# lumiere_ctrl_shematic.net
KiCad netlist of a schematic drawn in Altium Designer
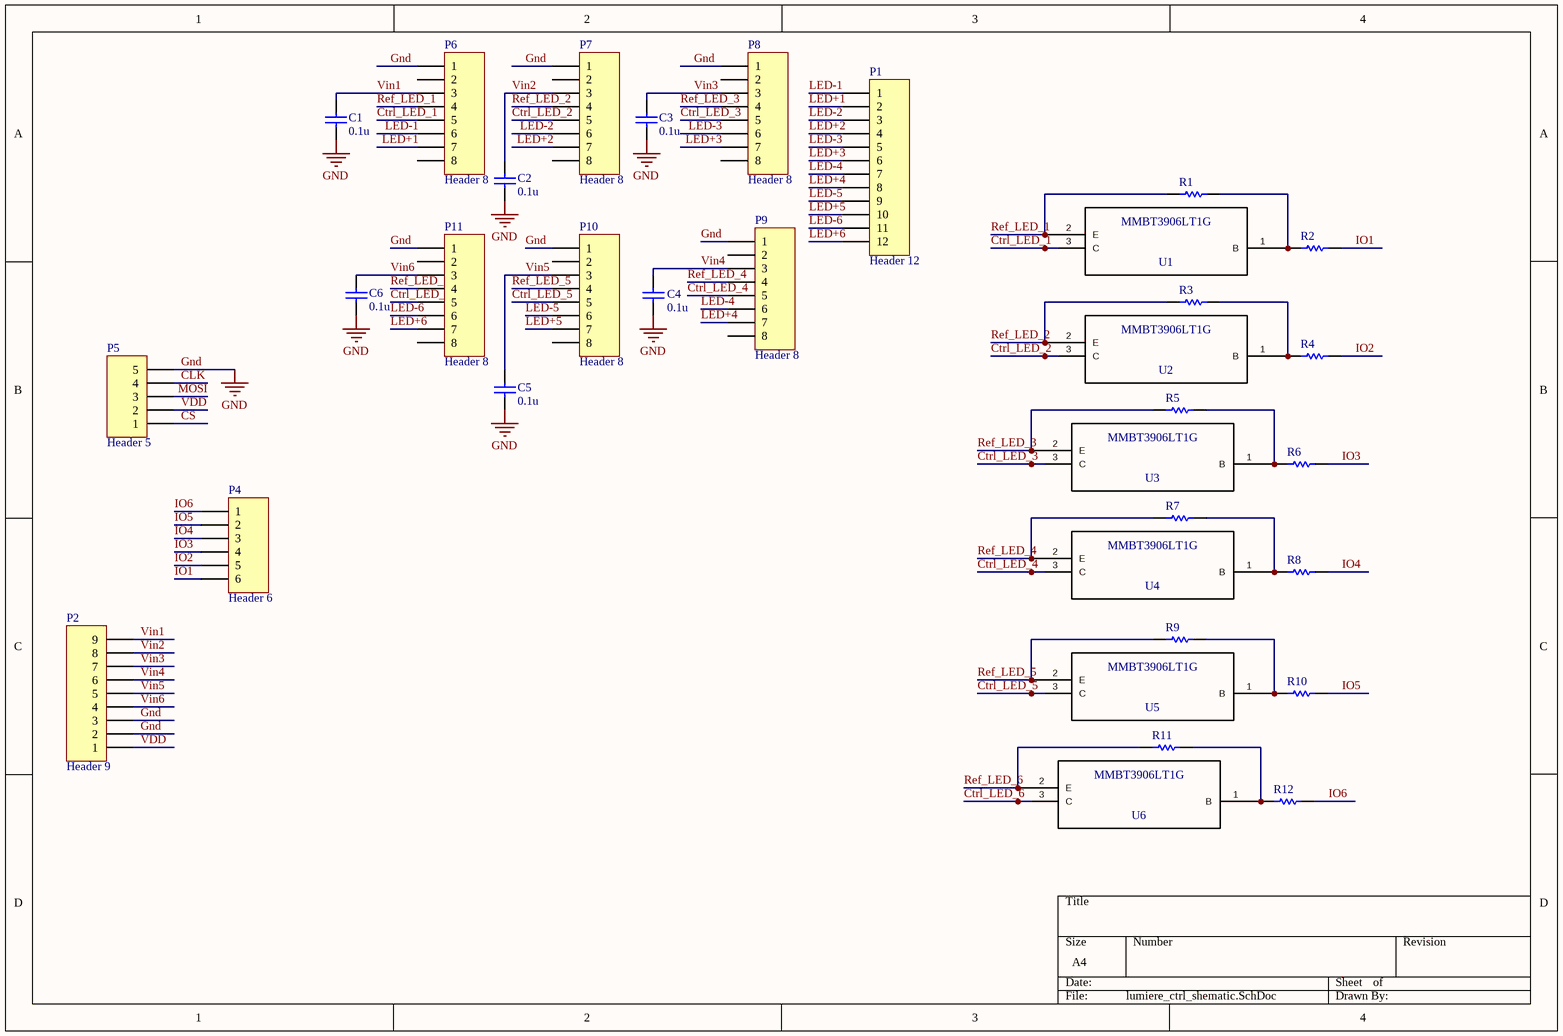
[diagram p0: lumiere_ctrl_shematic.SchDoc]

(export (version "E")
  (design (tool "Eeschema 10.0.6"))
  (components
    (comp (ref "C1")
      (value "0.1u")
      (footprint "CC1206N")
      (description "Capacitor")
      (fields (field (name "VOLTAGE") "50V") (field (name "Comment") "CapSMD"))
      (libsource (lib "S3_projet") (part "CapSMD"))
    )
    (comp (ref "C2")
      (value "0.1u")
      (footprint "CC1206N")
      (description "Capacitor")
      (fields (field (name "VOLTAGE") "50V") (field (name "Comment") "CapSMD"))
      (libsource (lib "S3_projet") (part "CapSMD"))
    )
    (comp (ref "C3")
      (value "0.1u")
      (footprint "CC1206N")
      (description "Capacitor")
      (fields (field (name "VOLTAGE") "50V") (field (name "Comment") "CapSMD"))
      (libsource (lib "S3_projet") (part "CapSMD"))
    )
    (comp (ref "C4")
      (value "0.1u")
      (footprint "CC1206N")
      (description "Capacitor")
      (fields (field (name "VOLTAGE") "50V") (field (name "Comment") "CapSMD"))
      (libsource (lib "S3_projet") (part "CapSMD"))
    )
    (comp (ref "C5")
      (value "0.1u")
      (footprint "CC1206N")
      (description "Capacitor")
      (fields (field (name "VOLTAGE") "50V") (field (name "Comment") "CapSMD"))
      (libsource (lib "S3_projet") (part "CapSMD"))
    )
    (comp (ref "C6")
      (value "0.1u")
      (footprint "CC1206N")
      (description "Capacitor")
      (fields (field (name "VOLTAGE") "50V") (field (name "Comment") "CapSMD"))
      (libsource (lib "S3_projet") (part "CapSMD"))
    )
    (comp (ref "P1")
      (value "Header 12")
      (footprint "Terminal block 12 pos")
      (description "Header, 12-Pin")
      (fields (field (name "PUBLISHER") "Altium Limited"))
      (libsource (lib "Miscellaneous Connectors") (part "Header 12"))
    )
    (comp (ref "P2")
      (value "Header 9")
      (footprint "Terminal block 9 pos")
      (description "Header, 9-Pin")
      (fields (field (name "PUBLISHER") "Altium Limited"))
      (libsource (lib "Miscellaneous Connectors") (part "Header 9"))
    )
    (comp (ref "P4")
      (value "Header 6")
      (footprint "HDR1X6")
      (description "Header, 6-Pin")
      (fields (field (name "PUBLISHER") "Altium Limited"))
      (libsource (lib "Miscellaneous Connectors") (part "Header 6"))
    )
    (comp (ref "P5")
      (value "Header 5")
      (footprint "HDR1X5")
      (description "Header, 5-Pin")
      (fields (field (name "PUBLISHER") "Altium Limited"))
      (libsource (lib "Miscellaneous Connectors") (part "Header 5"))
    )
    (comp (ref "P6")
      (value "Header 8")
      (footprint "HDR1X8")
      (description "Header, 8-Pin")
      (fields (field (name "PUBLISHER") "Altium Limited"))
      (libsource (lib "Miscellaneous Connectors") (part "Header 8"))
    )
    (comp (ref "P7")
      (value "Header 8")
      (footprint "HDR1X8")
      (description "Header, 8-Pin")
      (fields (field (name "PUBLISHER") "Altium Limited"))
      (libsource (lib "Miscellaneous Connectors") (part "Header 8"))
    )
    (comp (ref "P8")
      (value "Header 8")
      (footprint "HDR1X8")
      (description "Header, 8-Pin")
      (fields (field (name "PUBLISHER") "Altium Limited"))
      (libsource (lib "Miscellaneous Connectors") (part "Header 8"))
    )
    (comp (ref "P9")
      (value "Header 8")
      (footprint "HDR1X8")
      (description "Header, 8-Pin")
      (fields (field (name "PUBLISHER") "Altium Limited"))
      (libsource (lib "Miscellaneous Connectors") (part "Header 8"))
    )
    (comp (ref "P10")
      (value "Header 8")
      (footprint "HDR1X8")
      (description "Header, 8-Pin")
      (fields (field (name "PUBLISHER") "Altium Limited"))
      (libsource (lib "Miscellaneous Connectors") (part "Header 8"))
    )
    (comp (ref "P11")
      (value "Header 8")
      (footprint "HDR1X8")
      (description "Header, 8-Pin")
      (fields (field (name "PUBLISHER") "Altium Limited"))
      (libsource (lib "Miscellaneous Connectors") (part "Header 8"))
    )
    (comp (ref "R1")
      (value "ResSMD")
      (footprint "STA_RMCF1206")
      (libsource (lib "S3_projet") (part "ResSMD"))
    )
    (comp (ref "R2")
      (value "ResSMD")
      (footprint "STA_RMCF1206")
      (libsource (lib "S3_projet") (part "ResSMD"))
    )
    (comp (ref "R3")
      (value "ResSMD")
      (footprint "STA_RMCF1206")
      (libsource (lib "S3_projet") (part "ResSMD"))
    )
    (comp (ref "R4")
      (value "ResSMD")
      (footprint "STA_RMCF1206")
      (libsource (lib "S3_projet") (part "ResSMD"))
    )
    (comp (ref "R5")
      (value "ResSMD")
      (footprint "STA_RMCF1206")
      (libsource (lib "S3_projet") (part "ResSMD"))
    )
    (comp (ref "R6")
      (value "ResSMD")
      (footprint "STA_RMCF1206")
      (libsource (lib "S3_projet") (part "ResSMD"))
    )
    (comp (ref "R7")
      (value "ResSMD")
      (footprint "STA_RMCF1206")
      (libsource (lib "S3_projet") (part "ResSMD"))
    )
    (comp (ref "R8")
      (value "ResSMD")
      (footprint "STA_RMCF1206")
      (libsource (lib "S3_projet") (part "ResSMD"))
    )
    (comp (ref "R9")
      (value "ResSMD")
      (footprint "STA_RMCF1206")
      (libsource (lib "S3_projet") (part "ResSMD"))
    )
    (comp (ref "R10")
      (value "ResSMD")
      (footprint "STA_RMCF1206")
      (libsource (lib "S3_projet") (part "ResSMD"))
    )
    (comp (ref "R11")
      (value "ResSMD")
      (footprint "STA_RMCF1206")
      (libsource (lib "S3_projet") (part "ResSMD"))
    )
    (comp (ref "R12")
      (value "ResSMD")
      (footprint "STA_RMCF1206")
      (libsource (lib "S3_projet") (part "ResSMD"))
    )
    (comp (ref "U1")
      (value "MMBT3906LT1G")
      (footprint "SOT-23")
      (libsource (lib "AltiumV15") (part "MMBT3906LT1G"))
    )
    (comp (ref "U2")
      (value "MMBT3906LT1G")
      (footprint "SOT-23")
      (libsource (lib "AltiumV15") (part "MMBT3906LT1G"))
    )
    (comp (ref "U3")
      (value "MMBT3906LT1G")
      (footprint "SOT-23")
      (libsource (lib "AltiumV15") (part "MMBT3906LT1G"))
    )
    (comp (ref "U4")
      (value "MMBT3906LT1G")
      (footprint "SOT-23")
      (libsource (lib "AltiumV15") (part "MMBT3906LT1G"))
    )
    (comp (ref "U5")
      (value "MMBT3906LT1G")
      (footprint "SOT-23")
      (libsource (lib "AltiumV15") (part "MMBT3906LT1G"))
    )
    (comp (ref "U6")
      (value "MMBT3906LT1G")
      (footprint "SOT-23")
      (libsource (lib "AltiumV15") (part "MMBT3906LT1G"))
    )
  )
  (nets
    (net (code "1") (name "/CLK") (class "Default")
      (node (ref "P5") (pin "4") (pinfunction "4_4") (pintype "passive"))
    )
    (net (code "2") (name "/CS") (class "Default")
      (node (ref "P5") (pin "1") (pinfunction "1_1") (pintype "passive"))
    )
    (net (code "3") (name "/Ctrl_LED_1") (class "Default")
      (node (ref "P6") (pin "5") (pinfunction "5_5") (pintype "passive"))
      (node (ref "U1") (pin "3") (pinfunction "C_3") (pintype "passive"))
    )
    (net (code "4") (name "/Ctrl_LED_2") (class "Default")
      (node (ref "P7") (pin "5") (pinfunction "5_5") (pintype "passive"))
      (node (ref "U2") (pin "3") (pinfunction "C_3") (pintype "passive"))
    )
    (net (code "5") (name "/Ctrl_LED_3") (class "Default")
      (node (ref "P8") (pin "5") (pinfunction "5_5") (pintype "passive"))
      (node (ref "U3") (pin "3") (pinfunction "C_3") (pintype "passive"))
    )
    (net (code "6") (name "/Ctrl_LED_4") (class "Default")
      (node (ref "P9") (pin "5") (pinfunction "5_5") (pintype "passive"))
      (node (ref "U4") (pin "3") (pinfunction "C_3") (pintype "passive"))
    )
    (net (code "7") (name "/Ctrl_LED_5") (class "Default")
      (node (ref "P10") (pin "5") (pinfunction "5_5") (pintype "passive"))
      (node (ref "U5") (pin "3") (pinfunction "C_3") (pintype "passive"))
    )
    (net (code "8") (name "/Ctrl_LED_6") (class "Default")
      (node (ref "P11") (pin "5") (pinfunction "5_5") (pintype "passive"))
      (node (ref "U6") (pin "3") (pinfunction "C_3") (pintype "passive"))
    )
    (net (code "9") (name "/IO1") (class "Default")
      (node (ref "P4") (pin "6") (pinfunction "6_6") (pintype "passive"))
      (node (ref "R2") (pin "1") (pinfunction "1_1") (pintype "passive"))
    )
    (net (code "10") (name "/IO2") (class "Default")
      (node (ref "P4") (pin "5") (pinfunction "5_5") (pintype "passive"))
      (node (ref "R4") (pin "1") (pinfunction "1_1") (pintype "passive"))
    )
    (net (code "11") (name "/IO3") (class "Default")
      (node (ref "P4") (pin "4") (pinfunction "4_4") (pintype "passive"))
      (node (ref "R6") (pin "1") (pinfunction "1_1") (pintype "passive"))
    )
    (net (code "12") (name "/IO4") (class "Default")
      (node (ref "P4") (pin "3") (pinfunction "3_3") (pintype "passive"))
      (node (ref "R8") (pin "1") (pinfunction "1_1") (pintype "passive"))
    )
    (net (code "13") (name "/IO5") (class "Default")
      (node (ref "P4") (pin "2") (pinfunction "2_2") (pintype "passive"))
      (node (ref "R10") (pin "1") (pinfunction "1_1") (pintype "passive"))
    )
    (net (code "14") (name "/IO6") (class "Default")
      (node (ref "P4") (pin "1") (pinfunction "1_1") (pintype "passive"))
      (node (ref "R12") (pin "1") (pinfunction "1_1") (pintype "passive"))
    )
    (net (code "15") (name "/LED+1") (class "Default")
      (node (ref "P1") (pin "2") (pinfunction "2_2") (pintype "passive"))
      (node (ref "P6") (pin "7") (pinfunction "7_7") (pintype "passive"))
    )
    (net (code "16") (name "/LED+2") (class "Default")
      (node (ref "P1") (pin "4") (pinfunction "4_4") (pintype "passive"))
      (node (ref "P7") (pin "7") (pinfunction "7_7") (pintype "passive"))
    )
    (net (code "17") (name "/LED+3") (class "Default")
      (node (ref "P1") (pin "6") (pinfunction "6_6") (pintype "passive"))
      (node (ref "P8") (pin "7") (pinfunction "7_7") (pintype "passive"))
    )
    (net (code "18") (name "/LED+4") (class "Default")
      (node (ref "P1") (pin "8") (pinfunction "8_8") (pintype "passive"))
      (node (ref "P9") (pin "7") (pinfunction "7_7") (pintype "passive"))
    )
    (net (code "19") (name "/LED+5") (class "Default")
      (node (ref "P1") (pin "10") (pinfunction "10_10") (pintype "passive"))
      (node (ref "P10") (pin "7") (pinfunction "7_7") (pintype "passive"))
    )
    (net (code "20") (name "/LED+6") (class "Default")
      (node (ref "P1") (pin "12") (pinfunction "12_12") (pintype "passive"))
      (node (ref "P11") (pin "7") (pinfunction "7_7") (pintype "passive"))
    )
    (net (code "21") (name "/LED-1") (class "Default")
      (node (ref "P1") (pin "1") (pinfunction "1_1") (pintype "passive"))
      (node (ref "P6") (pin "6") (pinfunction "6_6") (pintype "passive"))
    )
    (net (code "22") (name "/LED-2") (class "Default")
      (node (ref "P1") (pin "3") (pinfunction "3_3") (pintype "passive"))
      (node (ref "P7") (pin "6") (pinfunction "6_6") (pintype "passive"))
    )
    (net (code "23") (name "/LED-3") (class "Default")
      (node (ref "P1") (pin "5") (pinfunction "5_5") (pintype "passive"))
      (node (ref "P8") (pin "6") (pinfunction "6_6") (pintype "passive"))
    )
    (net (code "24") (name "/LED-4") (class "Default")
      (node (ref "P1") (pin "7") (pinfunction "7_7") (pintype "passive"))
      (node (ref "P9") (pin "6") (pinfunction "6_6") (pintype "passive"))
    )
    (net (code "25") (name "/LED-5") (class "Default")
      (node (ref "P1") (pin "9") (pinfunction "9_9") (pintype "passive"))
      (node (ref "P10") (pin "6") (pinfunction "6_6") (pintype "passive"))
    )
    (net (code "26") (name "/LED-6") (class "Default")
      (node (ref "P1") (pin "11") (pinfunction "11_11") (pintype "passive"))
      (node (ref "P11") (pin "6") (pinfunction "6_6") (pintype "passive"))
    )
    (net (code "27") (name "/MOSI") (class "Default")
      (node (ref "P5") (pin "3") (pinfunction "3_3") (pintype "passive"))
    )
    (net (code "28") (name "/Ref_LED_1") (class "Default")
      (node (ref "P6") (pin "4") (pinfunction "4_4") (pintype "passive"))
      (node (ref "R1") (pin "2") (pinfunction "2_2") (pintype "passive"))
      (node (ref "U1") (pin "2") (pinfunction "E_2") (pintype "passive"))
    )
    (net (code "29") (name "/Ref_LED_2") (class "Default")
      (node (ref "P7") (pin "4") (pinfunction "4_4") (pintype "passive"))
      (node (ref "R3") (pin "2") (pinfunction "2_2") (pintype "passive"))
      (node (ref "U2") (pin "2") (pinfunction "E_2") (pintype "passive"))
    )
    (net (code "30") (name "/Ref_LED_3") (class "Default")
      (node (ref "P8") (pin "4") (pinfunction "4_4") (pintype "passive"))
      (node (ref "R5") (pin "2") (pinfunction "2_2") (pintype "passive"))
      (node (ref "U3") (pin "2") (pinfunction "E_2") (pintype "passive"))
    )
    (net (code "31") (name "/Ref_LED_4") (class "Default")
      (node (ref "P9") (pin "4") (pinfunction "4_4") (pintype "passive"))
      (node (ref "R7") (pin "2") (pinfunction "2_2") (pintype "passive"))
      (node (ref "U4") (pin "2") (pinfunction "E_2") (pintype "passive"))
    )
    (net (code "32") (name "/Ref_LED_5") (class "Default")
      (node (ref "P10") (pin "4") (pinfunction "4_4") (pintype "passive"))
      (node (ref "R9") (pin "2") (pinfunction "2_2") (pintype "passive"))
      (node (ref "U5") (pin "2") (pinfunction "E_2") (pintype "passive"))
    )
    (net (code "33") (name "/Ref_LED_6") (class "Default")
      (node (ref "P11") (pin "4") (pinfunction "4_4") (pintype "passive"))
      (node (ref "R11") (pin "2") (pinfunction "2_2") (pintype "passive"))
      (node (ref "U6") (pin "2") (pinfunction "E_2") (pintype "passive"))
    )
    (net (code "34") (name "/VDD") (class "Default")
      (node (ref "P2") (pin "1") (pinfunction "1_1") (pintype "passive"))
      (node (ref "P5") (pin "2") (pinfunction "2_2") (pintype "passive"))
    )
    (net (code "35") (name "/Vin1") (class "Default")
      (node (ref "C1") (pin "2") (pinfunction "2_2") (pintype "passive"))
      (node (ref "P2") (pin "9") (pinfunction "9_9") (pintype "passive"))
      (node (ref "P6") (pin "3") (pinfunction "3_3") (pintype "passive"))
    )
    (net (code "36") (name "/Vin2") (class "Default")
      (node (ref "C2") (pin "2") (pinfunction "2_2") (pintype "passive"))
      (node (ref "P2") (pin "8") (pinfunction "8_8") (pintype "passive"))
      (node (ref "P7") (pin "3") (pinfunction "3_3") (pintype "passive"))
    )
    (net (code "37") (name "/Vin3") (class "Default")
      (node (ref "C3") (pin "2") (pinfunction "2_2") (pintype "passive"))
      (node (ref "P2") (pin "7") (pinfunction "7_7") (pintype "passive"))
      (node (ref "P8") (pin "3") (pinfunction "3_3") (pintype "passive"))
    )
    (net (code "38") (name "/Vin4") (class "Default")
      (node (ref "C4") (pin "2") (pinfunction "2_2") (pintype "passive"))
      (node (ref "P2") (pin "6") (pinfunction "6_6") (pintype "passive"))
      (node (ref "P9") (pin "3") (pinfunction "3_3") (pintype "passive"))
    )
    (net (code "39") (name "/Vin5") (class "Default")
      (node (ref "C5") (pin "2") (pinfunction "2_2") (pintype "passive"))
      (node (ref "P10") (pin "3") (pinfunction "3_3") (pintype "passive"))
      (node (ref "P2") (pin "5") (pinfunction "5_5") (pintype "passive"))
    )
    (net (code "40") (name "/Vin6") (class "Default")
      (node (ref "C6") (pin "2") (pinfunction "2_2") (pintype "passive"))
      (node (ref "P11") (pin "3") (pinfunction "3_3") (pintype "passive"))
      (node (ref "P2") (pin "4") (pinfunction "4_4") (pintype "passive"))
    )
    (net (code "41") (name "GND") (class "Default")
      (node (ref "C1") (pin "1") (pinfunction "1_1") (pintype "passive"))
      (node (ref "C2") (pin "1") (pinfunction "1_1") (pintype "passive"))
      (node (ref "C3") (pin "1") (pinfunction "1_1") (pintype "passive"))
      (node (ref "C4") (pin "1") (pinfunction "1_1") (pintype "passive"))
      (node (ref "C5") (pin "1") (pinfunction "1_1") (pintype "passive"))
      (node (ref "C6") (pin "1") (pinfunction "1_1") (pintype "passive"))
      (node (ref "P10") (pin "1") (pinfunction "1_1") (pintype "passive"))
      (node (ref "P11") (pin "1") (pinfunction "1_1") (pintype "passive"))
      (node (ref "P2") (pin "2") (pinfunction "2_2") (pintype "passive"))
      (node (ref "P2") (pin "3") (pinfunction "3_3") (pintype "passive"))
      (node (ref "P5") (pin "5") (pinfunction "5_5") (pintype "passive"))
      (node (ref "P6") (pin "1") (pinfunction "1_1") (pintype "passive"))
      (node (ref "P7") (pin "1") (pinfunction "1_1") (pintype "passive"))
      (node (ref "P8") (pin "1") (pinfunction "1_1") (pintype "passive"))
      (node (ref "P9") (pin "1") (pinfunction "1_1") (pintype "passive"))
    )
    (net (code "42") (name "Net-(U1-B)") (class "Default")
      (node (ref "R1") (pin "1") (pinfunction "1_1") (pintype "passive"))
      (node (ref "R2") (pin "2") (pinfunction "2_2") (pintype "passive"))
      (node (ref "U1") (pin "1") (pinfunction "B_1") (pintype "passive"))
    )
    (net (code "43") (name "Net-(U2-B)") (class "Default")
      (node (ref "R3") (pin "1") (pinfunction "1_1") (pintype "passive"))
      (node (ref "R4") (pin "2") (pinfunction "2_2") (pintype "passive"))
      (node (ref "U2") (pin "1") (pinfunction "B_1") (pintype "passive"))
    )
    (net (code "44") (name "Net-(U3-B)") (class "Default")
      (node (ref "R5") (pin "1") (pinfunction "1_1") (pintype "passive"))
      (node (ref "R6") (pin "2") (pinfunction "2_2") (pintype "passive"))
      (node (ref "U3") (pin "1") (pinfunction "B_1") (pintype "passive"))
    )
    (net (code "45") (name "Net-(U4-B)") (class "Default")
      (node (ref "R7") (pin "1") (pinfunction "1_1") (pintype "passive"))
      (node (ref "R8") (pin "2") (pinfunction "2_2") (pintype "passive"))
      (node (ref "U4") (pin "1") (pinfunction "B_1") (pintype "passive"))
    )
    (net (code "46") (name "Net-(U5-B)") (class "Default")
      (node (ref "R10") (pin "2") (pinfunction "2_2") (pintype "passive"))
      (node (ref "R9") (pin "1") (pinfunction "1_1") (pintype "passive"))
      (node (ref "U5") (pin "1") (pinfunction "B_1") (pintype "passive"))
    )
    (net (code "47") (name "Net-(U6-B)") (class "Default")
      (node (ref "R11") (pin "1") (pinfunction "1_1") (pintype "passive"))
      (node (ref "R12") (pin "2") (pinfunction "2_2") (pintype "passive"))
      (node (ref "U6") (pin "1") (pinfunction "B_1") (pintype "passive"))
    )
    (net (code "48") (name "unconnected-(P6-Pad2)") (class "Default")
      (node (ref "P6") (pin "2") (pinfunction "2_2") (pintype "passive"))
    )
    (net (code "49") (name "unconnected-(P6-Pad8)") (class "Default")
      (node (ref "P6") (pin "8") (pinfunction "8_8") (pintype "passive"))
    )
    (net (code "50") (name "unconnected-(P7-Pad2)") (class "Default")
      (node (ref "P7") (pin "2") (pinfunction "2_2") (pintype "passive"))
    )
    (net (code "51") (name "unconnected-(P7-Pad8)") (class "Default")
      (node (ref "P7") (pin "8") (pinfunction "8_8") (pintype "passive"))
    )
    (net (code "52") (name "unconnected-(P8-Pad2)") (class "Default")
      (node (ref "P8") (pin "2") (pinfunction "2_2") (pintype "passive"))
    )
    (net (code "53") (name "unconnected-(P8-Pad8)") (class "Default")
      (node (ref "P8") (pin "8") (pinfunction "8_8") (pintype "passive"))
    )
    (net (code "54") (name "unconnected-(P9-Pad2)") (class "Default")
      (node (ref "P9") (pin "2") (pinfunction "2_2") (pintype "passive"))
    )
    (net (code "55") (name "unconnected-(P9-Pad8)") (class "Default")
      (node (ref "P9") (pin "8") (pinfunction "8_8") (pintype "passive"))
    )
    (net (code "56") (name "unconnected-(P10-Pad2)") (class "Default")
      (node (ref "P10") (pin "2") (pinfunction "2_2") (pintype "passive"))
    )
    (net (code "57") (name "unconnected-(P10-Pad8)") (class "Default")
      (node (ref "P10") (pin "8") (pinfunction "8_8") (pintype "passive"))
    )
    (net (code "58") (name "unconnected-(P11-Pad2)") (class "Default")
      (node (ref "P11") (pin "2") (pinfunction "2_2") (pintype "passive"))
    )
    (net (code "59") (name "unconnected-(P11-Pad8)") (class "Default")
      (node (ref "P11") (pin "8") (pinfunction "8_8") (pintype "passive"))
    )
  )
)
